# 03-Power.net
KiCad netlist of a schematic drawn in Altium Designer
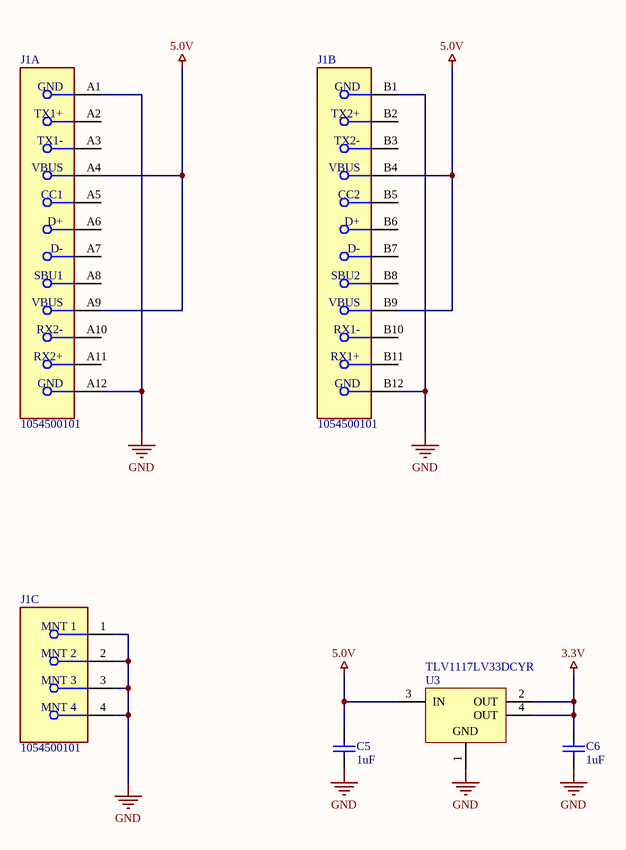
[diagram p0: 03-Power.SchDoc]

(export (version "E")
  (design (tool "Eeschema 10.0.6"))
  (components
    (comp (ref "C5")
      (value "C1206C105K3RACTU")
      (footprint "CAPC3216X180X50ML20T25")
      (description "Chip Capacitor, 1 uF, +/- 10%, 25 V, -55 to 125 degC, 1206 (3216 Metric), RoHS, Tape and Reel")
      (fields
        (field (name "CAPACITANCE") "1uF")
        (field (name "MANUFACTURER") "Kemet")
        (field (name "TOLERANCE") "10%")
      )
      (libsource (lib "Altium Content Vault") (part "CAP-NP-2"))
    )
    (comp (ref "C6")
      (value "C1206C105K3RACTU")
      (footprint "CAPC3216X180X50ML20T25")
      (description "Chip Capacitor, 1 uF, +/- 10%, 25 V, -55 to 125 degC, 1206 (3216 Metric), RoHS, Tape and Reel")
      (fields
        (field (name "CAPACITANCE") "1uF")
        (field (name "MANUFACTURER") "Kemet")
        (field (name "TOLERANCE") "10%")
      )
      (libsource (lib "Altium Content Vault") (part "CAP-NP-2"))
    )
    (comp (ref "J1")
      (value "1054500101")
      (footprint "FP-1054500101-MFG")
      (description "CONN RCP USB3.1 TYPEC 24P SMD RA")
      (fields
        (field (name "MANUFACTURER") "Molex")
        (field (name "OCTOPART") "https://octopart.com/105450-0101-molex-68082325")
      )
      (libsource (lib "Altium Content Vault") (part "9808b19ecaf079fb99eed69f0495cd0"))
    )
    (comp (ref "U3")
      (value "TLV1117LV33DCYR")
      (footprint "DCY0004A_N")
      (description "=Section")
      (fields (field (name "MANUFACTURER") "Texas Instruments"))
      (libsource (lib "Altium Content Vault") (part "TI-TLV1117LV33DCY4"))
    )
  )
  (nets
    (net (code "1") (name "3.3V") (class "Default")
      (node (ref "C6") (pin "2") (pinfunction "2_2") (pintype "passive"))
      (node (ref "U3") (pin "2") (pinfunction "OUT_2") (pintype "power_in"))
      (node (ref "U3") (pin "4") (pinfunction "OUT_4") (pintype "power_in"))
    )
    (net (code "2") (name "5.0V") (class "Default")
      (node (ref "C5") (pin "2") (pinfunction "2_2") (pintype "passive"))
      (node (ref "J1") (pin "A4") (pinfunction "VBUS_A4") (pintype "passive"))
      (node (ref "J1") (pin "A9") (pinfunction "VBUS_A9") (pintype "passive"))
      (node (ref "J1") (pin "B4") (pinfunction "VBUS_B4") (pintype "passive"))
      (node (ref "J1") (pin "B9") (pinfunction "VBUS_B9") (pintype "passive"))
      (node (ref "U3") (pin "3") (pinfunction "IN_3") (pintype "power_in"))
    )
    (net (code "3") (name "GND") (class "Default")
      (node (ref "C5") (pin "1") (pinfunction "1_1") (pintype "passive"))
      (node (ref "C6") (pin "1") (pinfunction "1_1") (pintype "passive"))
      (node (ref "J1") (pin "1") (pinfunction "MNT_1_1") (pintype "passive"))
      (node (ref "J1") (pin "2") (pinfunction "MNT_2_2") (pintype "passive"))
      (node (ref "J1") (pin "3") (pinfunction "MNT_3_3") (pintype "passive"))
      (node (ref "J1") (pin "4") (pinfunction "MNT_4_4") (pintype "passive"))
      (node (ref "J1") (pin "A1") (pinfunction "GND_A1") (pintype "passive"))
      (node (ref "J1") (pin "A12") (pinfunction "GND_A12") (pintype "passive"))
      (node (ref "J1") (pin "B1") (pinfunction "GND_B1") (pintype "passive"))
      (node (ref "J1") (pin "B12") (pinfunction "GND_B12") (pintype "passive"))
      (node (ref "U3") (pin "1") (pinfunction "GND_1") (pintype "power_in"))
    )
    (net (code "4") (name "unconnected-(J1A-CC1-PadA5)") (class "Default")
      (node (ref "J1") (pin "A5") (pinfunction "CC1_A5") (pintype "passive"))
    )
    (net (code "5") (name "unconnected-(J1A-D+-PadA6)") (class "Default")
      (node (ref "J1") (pin "A6") (pinfunction "D+_A6") (pintype "passive"))
    )
    (net (code "6") (name "unconnected-(J1A-D--PadA7)") (class "Default")
      (node (ref "J1") (pin "A7") (pinfunction "D-_A7") (pintype "passive"))
    )
    (net (code "7") (name "unconnected-(J1A-RX2+-PadA11)") (class "Default")
      (node (ref "J1") (pin "A11") (pinfunction "RX2+_A11") (pintype "passive"))
    )
    (net (code "8") (name "unconnected-(J1A-RX2--PadA10)") (class "Default")
      (node (ref "J1") (pin "A10") (pinfunction "RX2-_A10") (pintype "passive"))
    )
    (net (code "9") (name "unconnected-(J1A-SBU1-PadA8)") (class "Default")
      (node (ref "J1") (pin "A8") (pinfunction "SBU1_A8") (pintype "passive"))
    )
    (net (code "10") (name "unconnected-(J1A-TX1+-PadA2)") (class "Default")
      (node (ref "J1") (pin "A2") (pinfunction "TX1+_A2") (pintype "passive"))
    )
    (net (code "11") (name "unconnected-(J1A-TX1--PadA3)") (class "Default")
      (node (ref "J1") (pin "A3") (pinfunction "TX1-_A3") (pintype "passive"))
    )
    (net (code "12") (name "unconnected-(J1B-CC2-PadB5)") (class "Default")
      (node (ref "J1") (pin "B5") (pinfunction "CC2_B5") (pintype "passive"))
    )
    (net (code "13") (name "unconnected-(J1B-D+-PadB6)") (class "Default")
      (node (ref "J1") (pin "B6") (pinfunction "D+_B6") (pintype "passive"))
    )
    (net (code "14") (name "unconnected-(J1B-D--PadB7)") (class "Default")
      (node (ref "J1") (pin "B7") (pinfunction "D-_B7") (pintype "passive"))
    )
    (net (code "15") (name "unconnected-(J1B-RX1+-PadB11)") (class "Default")
      (node (ref "J1") (pin "B11") (pinfunction "RX1+_B11") (pintype "passive"))
    )
    (net (code "16") (name "unconnected-(J1B-RX1--PadB10)") (class "Default")
      (node (ref "J1") (pin "B10") (pinfunction "RX1-_B10") (pintype "passive"))
    )
    (net (code "17") (name "unconnected-(J1B-SBU2-PadB8)") (class "Default")
      (node (ref "J1") (pin "B8") (pinfunction "SBU2_B8") (pintype "passive"))
    )
    (net (code "18") (name "unconnected-(J1B-TX2+-PadB2)") (class "Default")
      (node (ref "J1") (pin "B2") (pinfunction "TX2+_B2") (pintype "passive"))
    )
    (net (code "19") (name "unconnected-(J1B-TX2--PadB3)") (class "Default")
      (node (ref "J1") (pin "B3") (pinfunction "TX2-_B3") (pintype "passive"))
    )
  )
)
